# PDSP-py-2.net
KiCad netlist of a schematic drawn in EAGLE
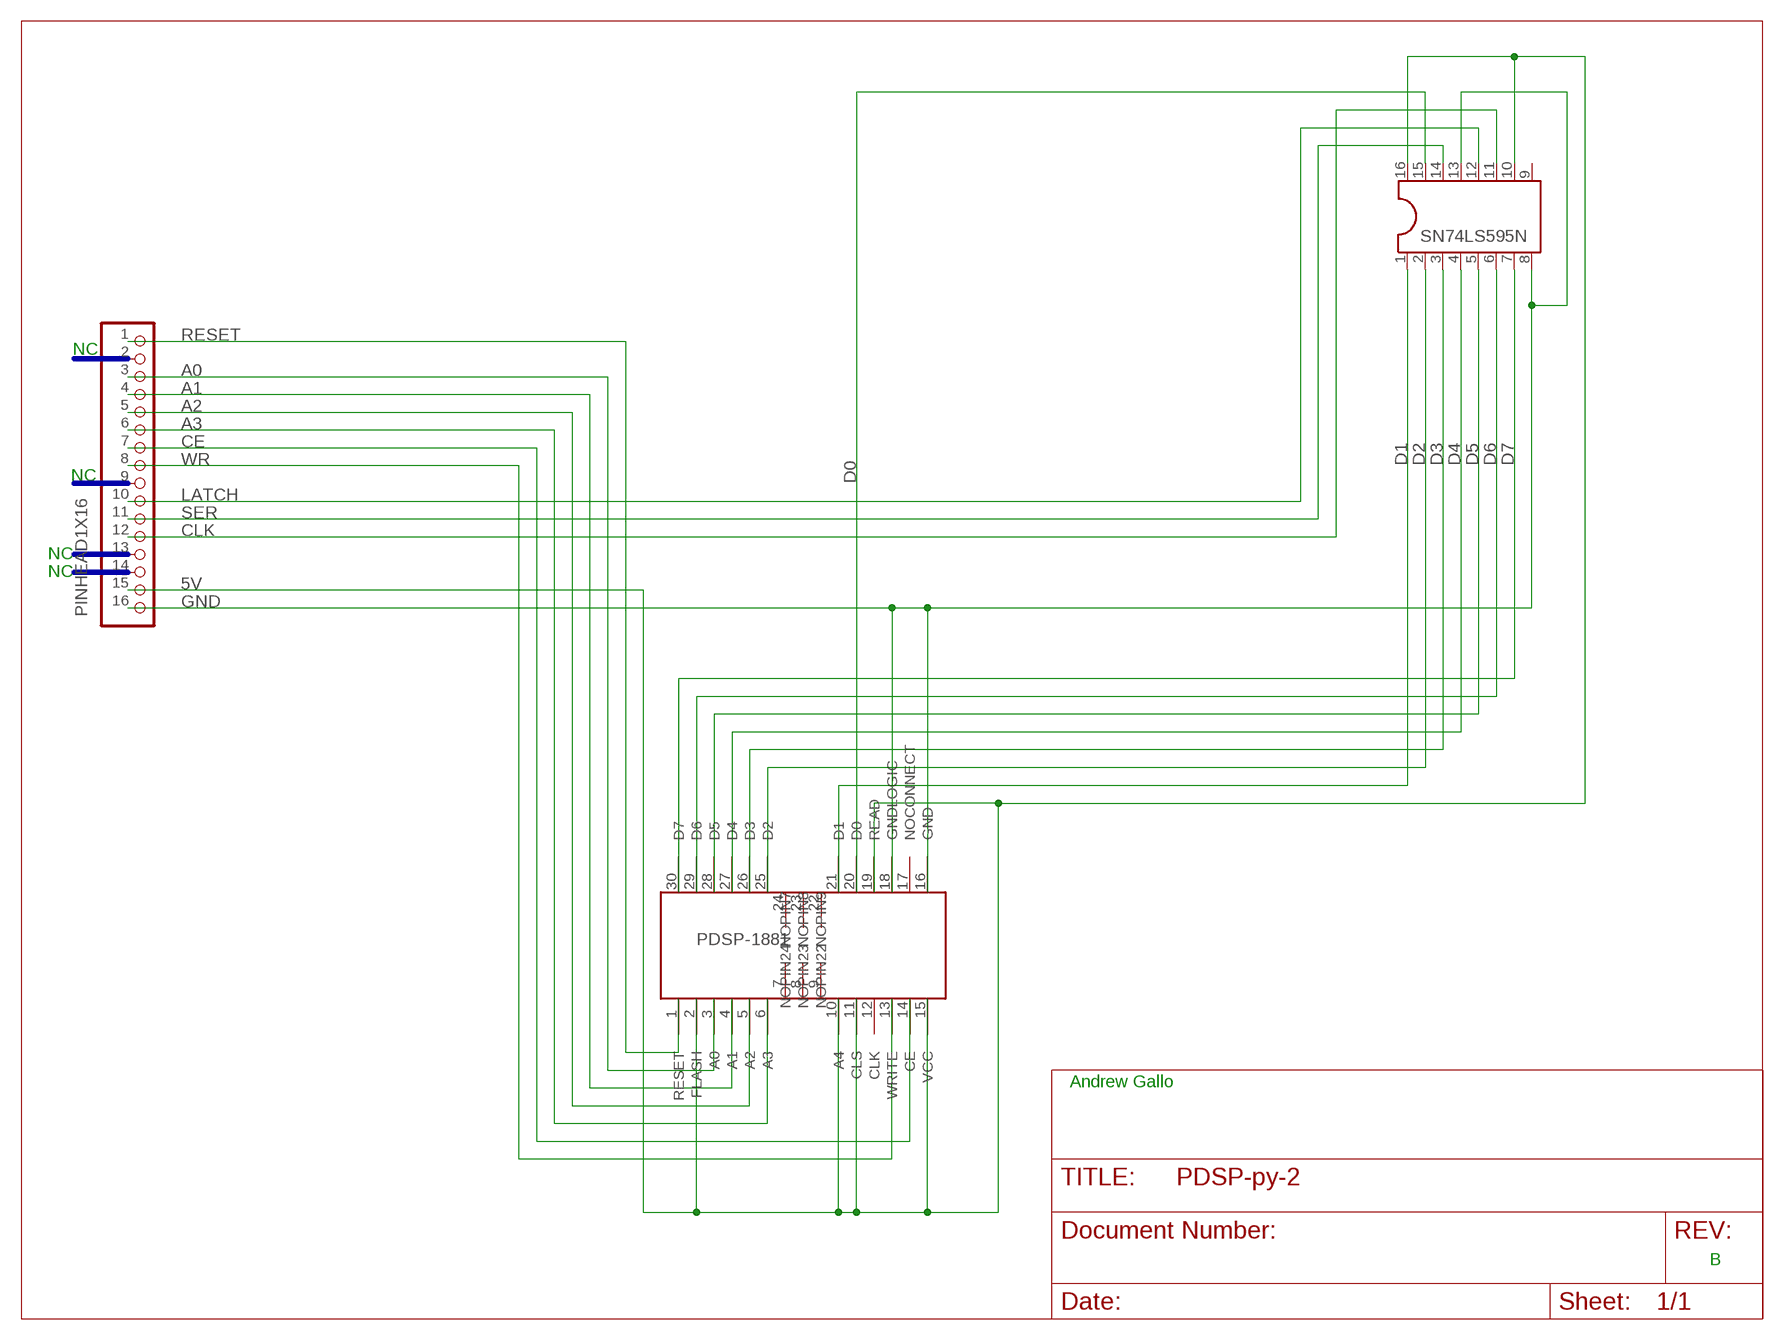
[diagram p0: schematic, sheet 1]

(export (version "E")
  (design (tool "Eeschema 10.0.6"))
  (components
    (comp (ref "PDSP-1881")
      (value "AKG-PDSP-188-DEV")
      (footprint "eagle-import:AKG-PDSP-188X-PAC")
      (libsource (lib "eagle-import") (part "AKG-PDSP-188-DEV"))
    )
    (comp (ref "PINHEAD1X16")
      (value "PINHD-1X16")
      (footprint "eagle-import:1X16")
      (libsource (lib "eagle-import") (part "PINHD-1X16"))
    )
    (comp (ref "SN74LS595N")
      (value "DIL16")
      (footprint "eagle-import:DIL16")
      (libsource (lib "eagle-import") (part "DIL16"))
    )
  )
  (nets
    (net (code "1") (name "/5V") (class "Default")
      (node (ref "PDSP-1881") (pin "10") (pinfunction "A4_10") (pintype "bidirectional"))
      (node (ref "PDSP-1881") (pin "11") (pinfunction "CLS_11") (pintype "bidirectional"))
      (node (ref "PDSP-1881") (pin "15") (pinfunction "VCC_15") (pintype "bidirectional"))
      (node (ref "PDSP-1881") (pin "19") (pinfunction "READ_19") (pintype "bidirectional"))
      (node (ref "PDSP-1881") (pin "2") (pinfunction "FLASH_2") (pintype "bidirectional"))
      (node (ref "PINHEAD1X16") (pin "15") (pinfunction "15_15") (pintype "passive"))
      (node (ref "SN74LS595N") (pin "10") (pinfunction "10_10") (pintype "passive"))
      (node (ref "SN74LS595N") (pin "16") (pinfunction "16_16") (pintype "passive"))
    )
    (net (code "2") (name "/A0") (class "Default")
      (node (ref "PDSP-1881") (pin "3") (pinfunction "A0_3") (pintype "bidirectional"))
      (node (ref "PINHEAD1X16") (pin "3") (pinfunction "3_3") (pintype "passive"))
    )
    (net (code "3") (name "/A1") (class "Default")
      (node (ref "PDSP-1881") (pin "4") (pinfunction "A1_4") (pintype "bidirectional"))
      (node (ref "PINHEAD1X16") (pin "4") (pinfunction "4_4") (pintype "passive"))
    )
    (net (code "4") (name "/A2") (class "Default")
      (node (ref "PDSP-1881") (pin "5") (pinfunction "A2_5") (pintype "bidirectional"))
      (node (ref "PINHEAD1X16") (pin "5") (pinfunction "5_5") (pintype "passive"))
    )
    (net (code "5") (name "/A3") (class "Default")
      (node (ref "PDSP-1881") (pin "6") (pinfunction "A3_6") (pintype "bidirectional"))
      (node (ref "PINHEAD1X16") (pin "6") (pinfunction "6_6") (pintype "passive"))
    )
    (net (code "6") (name "/CE") (class "Default")
      (node (ref "PDSP-1881") (pin "14") (pinfunction "CE_14") (pintype "bidirectional"))
      (node (ref "PINHEAD1X16") (pin "7") (pinfunction "7_7") (pintype "passive"))
    )
    (net (code "7") (name "/CLK") (class "Default")
      (node (ref "PINHEAD1X16") (pin "12") (pinfunction "12_12") (pintype "passive"))
      (node (ref "SN74LS595N") (pin "11") (pinfunction "11_11") (pintype "passive"))
    )
    (net (code "8") (name "/D0") (class "Default")
      (node (ref "PDSP-1881") (pin "20") (pinfunction "D0_20") (pintype "bidirectional"))
      (node (ref "SN74LS595N") (pin "15") (pinfunction "15_15") (pintype "passive"))
    )
    (net (code "9") (name "/D1") (class "Default")
      (node (ref "PDSP-1881") (pin "21") (pinfunction "D1_21") (pintype "bidirectional"))
      (node (ref "SN74LS595N") (pin "1") (pinfunction "1_1") (pintype "passive"))
    )
    (net (code "10") (name "/D2") (class "Default")
      (node (ref "PDSP-1881") (pin "25") (pinfunction "D2_25") (pintype "bidirectional"))
      (node (ref "SN74LS595N") (pin "2") (pinfunction "2_2") (pintype "passive"))
    )
    (net (code "11") (name "/D3") (class "Default")
      (node (ref "PDSP-1881") (pin "26") (pinfunction "D3_26") (pintype "bidirectional"))
      (node (ref "SN74LS595N") (pin "3") (pinfunction "3_3") (pintype "passive"))
    )
    (net (code "12") (name "/D4") (class "Default")
      (node (ref "PDSP-1881") (pin "27") (pinfunction "D4_27") (pintype "bidirectional"))
      (node (ref "SN74LS595N") (pin "4") (pinfunction "4_4") (pintype "passive"))
    )
    (net (code "13") (name "/D5") (class "Default")
      (node (ref "PDSP-1881") (pin "28") (pinfunction "D5_28") (pintype "bidirectional"))
      (node (ref "SN74LS595N") (pin "5") (pinfunction "5_5") (pintype "passive"))
    )
    (net (code "14") (name "/D6") (class "Default")
      (node (ref "PDSP-1881") (pin "29") (pinfunction "D6_29") (pintype "bidirectional"))
      (node (ref "SN74LS595N") (pin "6") (pinfunction "6_6") (pintype "passive"))
    )
    (net (code "15") (name "/D7") (class "Default")
      (node (ref "PDSP-1881") (pin "30") (pinfunction "D7_30") (pintype "bidirectional"))
      (node (ref "SN74LS595N") (pin "7") (pinfunction "7_7") (pintype "passive"))
    )
    (net (code "16") (name "/GND") (class "Default")
      (node (ref "PDSP-1881") (pin "16") (pinfunction "GND_16") (pintype "bidirectional"))
      (node (ref "PDSP-1881") (pin "18") (pinfunction "GNDLOGIC_18") (pintype "bidirectional"))
      (node (ref "PINHEAD1X16") (pin "16") (pinfunction "16_16") (pintype "passive"))
      (node (ref "SN74LS595N") (pin "13") (pinfunction "13_13") (pintype "passive"))
      (node (ref "SN74LS595N") (pin "8") (pinfunction "8_8") (pintype "passive"))
    )
    (net (code "17") (name "/LATCH") (class "Default")
      (node (ref "PINHEAD1X16") (pin "10") (pinfunction "10_10") (pintype "passive"))
      (node (ref "SN74LS595N") (pin "12") (pinfunction "12_12") (pintype "passive"))
    )
    (net (code "18") (name "/RESET") (class "Default")
      (node (ref "PDSP-1881") (pin "1") (pinfunction "RESET_1") (pintype "bidirectional"))
      (node (ref "PINHEAD1X16") (pin "1") (pinfunction "1_1") (pintype "passive"))
    )
    (net (code "19") (name "/SER") (class "Default")
      (node (ref "PINHEAD1X16") (pin "11") (pinfunction "11_11") (pintype "passive"))
      (node (ref "SN74LS595N") (pin "14") (pinfunction "14_14") (pintype "passive"))
    )
    (net (code "20") (name "/WR") (class "Default")
      (node (ref "PDSP-1881") (pin "13") (pinfunction "WRITE_13") (pintype "bidirectional"))
      (node (ref "PINHEAD1X16") (pin "8") (pinfunction "8_8") (pintype "passive"))
    )
    (net (code "21") (name "unconnected-(PDSP-1881-CLK-Pad12)") (class "Default")
      (node (ref "PDSP-1881") (pin "12") (pinfunction "CLK_12") (pintype "bidirectional"))
    )
    (net (code "22") (name "unconnected-(PDSP-1881-NOCONNECT-Pad17)") (class "Default")
      (node (ref "PDSP-1881") (pin "17") (pinfunction "NOCONNECT_17") (pintype "bidirectional"))
    )
    (net (code "23") (name "unconnected-(PDSP-1881-NOPIN7-Pad7)") (class "Default")
      (node (ref "PDSP-1881") (pin "7") (pinfunction "NOPIN7_7") (pintype "bidirectional"))
    )
    (net (code "24") (name "unconnected-(PDSP-1881-NOPIN8-Pad8)") (class "Default")
      (node (ref "PDSP-1881") (pin "8") (pinfunction "NOPIN8_8") (pintype "bidirectional"))
    )
    (net (code "25") (name "unconnected-(PDSP-1881-NOPIN9-Pad9)") (class "Default")
      (node (ref "PDSP-1881") (pin "9") (pinfunction "NOPIN9_9") (pintype "bidirectional"))
    )
    (net (code "26") (name "unconnected-(PDSP-1881-NOPIN22-Pad22)") (class "Default")
      (node (ref "PDSP-1881") (pin "22") (pinfunction "NOPIN22_22") (pintype "bidirectional"))
    )
    (net (code "27") (name "unconnected-(PDSP-1881-NOPIN23-Pad23)") (class "Default")
      (node (ref "PDSP-1881") (pin "23") (pinfunction "NOPIN23_23") (pintype "bidirectional"))
    )
    (net (code "28") (name "unconnected-(PDSP-1881-NOPIN24-Pad24)") (class "Default")
      (node (ref "PDSP-1881") (pin "24") (pinfunction "NOPIN24_24") (pintype "bidirectional"))
    )
    (net (code "29") (name "unconnected-(PINHEAD1X16-Pad2)") (class "Default")
      (node (ref "PINHEAD1X16") (pin "2") (pinfunction "2_2") (pintype "passive"))
    )
    (net (code "30") (name "unconnected-(PINHEAD1X16-Pad9)") (class "Default")
      (node (ref "PINHEAD1X16") (pin "9") (pinfunction "9_9") (pintype "passive"))
    )
    (net (code "31") (name "unconnected-(PINHEAD1X16-Pad13)") (class "Default")
      (node (ref "PINHEAD1X16") (pin "13") (pinfunction "13_13") (pintype "passive"))
    )
    (net (code "32") (name "unconnected-(PINHEAD1X16-Pad14)") (class "Default")
      (node (ref "PINHEAD1X16") (pin "14") (pinfunction "14_14") (pintype "passive"))
    )
    (net (code "33") (name "unconnected-(SN74LS595N-Pad9)") (class "Default")
      (node (ref "SN74LS595N") (pin "9") (pinfunction "9_9") (pintype "passive"))
    )
  )
)
